# LEDMatrix_buffered.net
KiCad netlist of a schematic drawn in EAGLE
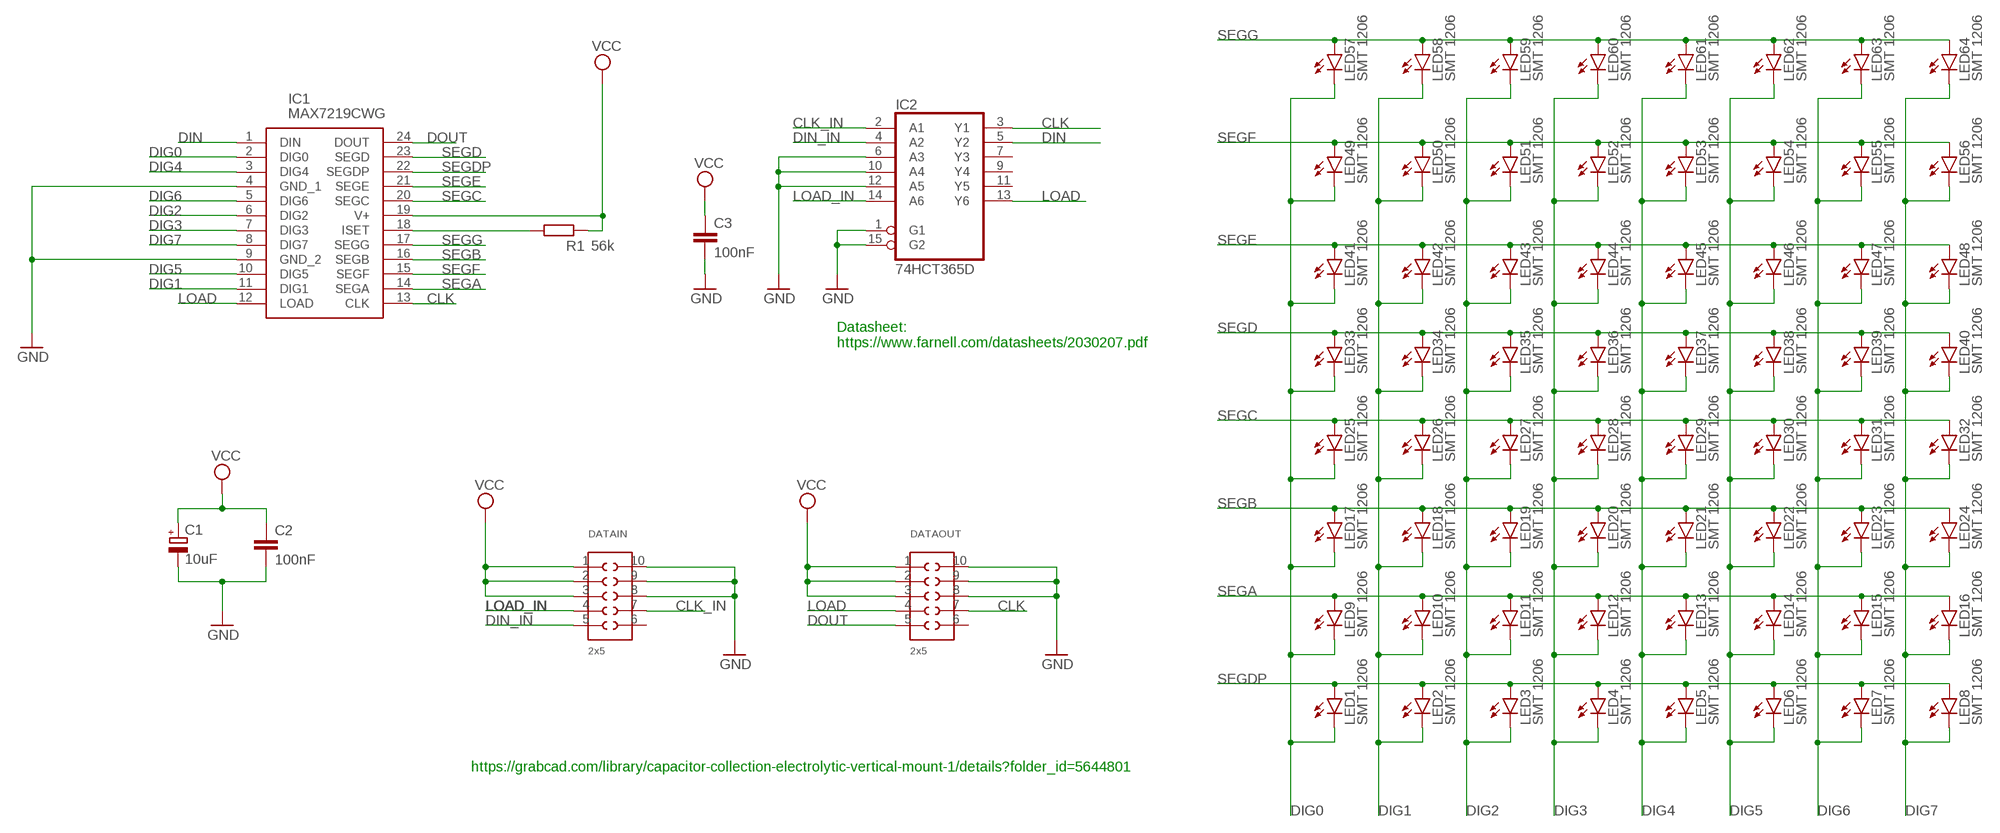
[diagram p0: schematic, sheet 1]

(export (version "E")
  (design (tool "Eeschema 10.0.6"))
  (components
    (comp (ref "C1")
      (value "10uF")
      (footprint "eagle-import:E5-8,5")
      (libsource (lib "eagle-import") (part "CPOL-EUE5-8.5"))
    )
    (comp (ref "C2")
      (value "100nF")
      (footprint "eagle-import:C1206")
      (libsource (lib "eagle-import") (part "C-EUC1206"))
    )
    (comp (ref "C3")
      (value "100nF")
      (footprint "eagle-import:C1206")
      (libsource (lib "eagle-import") (part "C-EUC1206"))
    )
    (comp (ref "DATAIN")
      (value "2x5")
      (footprint "eagle-import:610X1021121")
      (libsource (lib "eagle-import") (part "610X1021121"))
    )
    (comp (ref "DATAOUT")
      (value "2x5")
      (footprint "eagle-import:610X1021121")
      (libsource (lib "eagle-import") (part "610X1021121"))
    )
    (comp (ref "IC1")
      (value "MAX7219CWG")
      (footprint "eagle-import:SOIC127P1032X265-24N")
      (libsource (lib "eagle-import") (part "MAX7219CWG"))
    )
    (comp (ref "IC2")
      (value "74HCT365D")
      (footprint "eagle-import:SO16")
      (fields (field (name "SPICEPREFIX") "X"))
      (libsource (lib "eagle-import") (part "74365DHCT"))
    )
    (comp (ref "LED1")
      (value "SMT 1206")
      (footprint "eagle-import:CHIPLED_1206")
      (libsource (lib "eagle-import") (part "LEDCHIPLED_1206"))
    )
    (comp (ref "LED2")
      (value "SMT 1206")
      (footprint "eagle-import:CHIPLED_1206")
      (libsource (lib "eagle-import") (part "LEDCHIPLED_1206"))
    )
    (comp (ref "LED3")
      (value "SMT 1206")
      (footprint "eagle-import:CHIPLED_1206")
      (libsource (lib "eagle-import") (part "LEDCHIPLED_1206"))
    )
    (comp (ref "LED4")
      (value "SMT 1206")
      (footprint "eagle-import:CHIPLED_1206")
      (libsource (lib "eagle-import") (part "LEDCHIPLED_1206"))
    )
    (comp (ref "LED5")
      (value "SMT 1206")
      (footprint "eagle-import:CHIPLED_1206")
      (libsource (lib "eagle-import") (part "LEDCHIPLED_1206"))
    )
    (comp (ref "LED6")
      (value "SMT 1206")
      (footprint "eagle-import:CHIPLED_1206")
      (libsource (lib "eagle-import") (part "LEDCHIPLED_1206"))
    )
    (comp (ref "LED7")
      (value "SMT 1206")
      (footprint "eagle-import:CHIPLED_1206")
      (libsource (lib "eagle-import") (part "LEDCHIPLED_1206"))
    )
    (comp (ref "LED8")
      (value "SMT 1206")
      (footprint "eagle-import:CHIPLED_1206")
      (libsource (lib "eagle-import") (part "LEDCHIPLED_1206"))
    )
    (comp (ref "LED9")
      (value "SMT 1206")
      (footprint "eagle-import:CHIPLED_1206")
      (libsource (lib "eagle-import") (part "LEDCHIPLED_1206"))
    )
    (comp (ref "LED10")
      (value "SMT 1206")
      (footprint "eagle-import:CHIPLED_1206")
      (libsource (lib "eagle-import") (part "LEDCHIPLED_1206"))
    )
    (comp (ref "LED11")
      (value "SMT 1206")
      (footprint "eagle-import:CHIPLED_1206")
      (libsource (lib "eagle-import") (part "LEDCHIPLED_1206"))
    )
    (comp (ref "LED12")
      (value "SMT 1206")
      (footprint "eagle-import:CHIPLED_1206")
      (libsource (lib "eagle-import") (part "LEDCHIPLED_1206"))
    )
    (comp (ref "LED13")
      (value "SMT 1206")
      (footprint "eagle-import:CHIPLED_1206")
      (libsource (lib "eagle-import") (part "LEDCHIPLED_1206"))
    )
    (comp (ref "LED14")
      (value "SMT 1206")
      (footprint "eagle-import:CHIPLED_1206")
      (libsource (lib "eagle-import") (part "LEDCHIPLED_1206"))
    )
    (comp (ref "LED15")
      (value "SMT 1206")
      (footprint "eagle-import:CHIPLED_1206")
      (libsource (lib "eagle-import") (part "LEDCHIPLED_1206"))
    )
    (comp (ref "LED16")
      (value "SMT 1206")
      (footprint "eagle-import:CHIPLED_1206")
      (libsource (lib "eagle-import") (part "LEDCHIPLED_1206"))
    )
    (comp (ref "LED17")
      (value "SMT 1206")
      (footprint "eagle-import:CHIPLED_1206")
      (libsource (lib "eagle-import") (part "LEDCHIPLED_1206"))
    )
    (comp (ref "LED18")
      (value "SMT 1206")
      (footprint "eagle-import:CHIPLED_1206")
      (libsource (lib "eagle-import") (part "LEDCHIPLED_1206"))
    )
    (comp (ref "LED19")
      (value "SMT 1206")
      (footprint "eagle-import:CHIPLED_1206")
      (libsource (lib "eagle-import") (part "LEDCHIPLED_1206"))
    )
    (comp (ref "LED20")
      (value "SMT 1206")
      (footprint "eagle-import:CHIPLED_1206")
      (libsource (lib "eagle-import") (part "LEDCHIPLED_1206"))
    )
    (comp (ref "LED21")
      (value "SMT 1206")
      (footprint "eagle-import:CHIPLED_1206")
      (libsource (lib "eagle-import") (part "LEDCHIPLED_1206"))
    )
    (comp (ref "LED22")
      (value "SMT 1206")
      (footprint "eagle-import:CHIPLED_1206")
      (libsource (lib "eagle-import") (part "LEDCHIPLED_1206"))
    )
    (comp (ref "LED23")
      (value "SMT 1206")
      (footprint "eagle-import:CHIPLED_1206")
      (libsource (lib "eagle-import") (part "LEDCHIPLED_1206"))
    )
    (comp (ref "LED24")
      (value "SMT 1206")
      (footprint "eagle-import:CHIPLED_1206")
      (libsource (lib "eagle-import") (part "LEDCHIPLED_1206"))
    )
    (comp (ref "LED25")
      (value "SMT 1206")
      (footprint "eagle-import:CHIPLED_1206")
      (libsource (lib "eagle-import") (part "LEDCHIPLED_1206"))
    )
    (comp (ref "LED26")
      (value "SMT 1206")
      (footprint "eagle-import:CHIPLED_1206")
      (libsource (lib "eagle-import") (part "LEDCHIPLED_1206"))
    )
    (comp (ref "LED27")
      (value "SMT 1206")
      (footprint "eagle-import:CHIPLED_1206")
      (libsource (lib "eagle-import") (part "LEDCHIPLED_1206"))
    )
    (comp (ref "LED28")
      (value "SMT 1206")
      (footprint "eagle-import:CHIPLED_1206")
      (libsource (lib "eagle-import") (part "LEDCHIPLED_1206"))
    )
    (comp (ref "LED29")
      (value "SMT 1206")
      (footprint "eagle-import:CHIPLED_1206")
      (libsource (lib "eagle-import") (part "LEDCHIPLED_1206"))
    )
    (comp (ref "LED30")
      (value "SMT 1206")
      (footprint "eagle-import:CHIPLED_1206")
      (libsource (lib "eagle-import") (part "LEDCHIPLED_1206"))
    )
    (comp (ref "LED31")
      (value "SMT 1206")
      (footprint "eagle-import:CHIPLED_1206")
      (libsource (lib "eagle-import") (part "LEDCHIPLED_1206"))
    )
    (comp (ref "LED32")
      (value "SMT 1206")
      (footprint "eagle-import:CHIPLED_1206")
      (libsource (lib "eagle-import") (part "LEDCHIPLED_1206"))
    )
    (comp (ref "LED33")
      (value "SMT 1206")
      (footprint "eagle-import:CHIPLED_1206")
      (libsource (lib "eagle-import") (part "LEDCHIPLED_1206"))
    )
    (comp (ref "LED34")
      (value "SMT 1206")
      (footprint "eagle-import:CHIPLED_1206")
      (libsource (lib "eagle-import") (part "LEDCHIPLED_1206"))
    )
    (comp (ref "LED35")
      (value "SMT 1206")
      (footprint "eagle-import:CHIPLED_1206")
      (libsource (lib "eagle-import") (part "LEDCHIPLED_1206"))
    )
    (comp (ref "LED36")
      (value "SMT 1206")
      (footprint "eagle-import:CHIPLED_1206")
      (libsource (lib "eagle-import") (part "LEDCHIPLED_1206"))
    )
    (comp (ref "LED37")
      (value "SMT 1206")
      (footprint "eagle-import:CHIPLED_1206")
      (libsource (lib "eagle-import") (part "LEDCHIPLED_1206"))
    )
    (comp (ref "LED38")
      (value "SMT 1206")
      (footprint "eagle-import:CHIPLED_1206")
      (libsource (lib "eagle-import") (part "LEDCHIPLED_1206"))
    )
    (comp (ref "LED39")
      (value "SMT 1206")
      (footprint "eagle-import:CHIPLED_1206")
      (libsource (lib "eagle-import") (part "LEDCHIPLED_1206"))
    )
    (comp (ref "LED40")
      (value "SMT 1206")
      (footprint "eagle-import:CHIPLED_1206")
      (libsource (lib "eagle-import") (part "LEDCHIPLED_1206"))
    )
    (comp (ref "LED41")
      (value "SMT 1206")
      (footprint "eagle-import:CHIPLED_1206")
      (libsource (lib "eagle-import") (part "LEDCHIPLED_1206"))
    )
    (comp (ref "LED42")
      (value "SMT 1206")
      (footprint "eagle-import:CHIPLED_1206")
      (libsource (lib "eagle-import") (part "LEDCHIPLED_1206"))
    )
    (comp (ref "LED43")
      (value "SMT 1206")
      (footprint "eagle-import:CHIPLED_1206")
      (libsource (lib "eagle-import") (part "LEDCHIPLED_1206"))
    )
    (comp (ref "LED44")
      (value "SMT 1206")
      (footprint "eagle-import:CHIPLED_1206")
      (libsource (lib "eagle-import") (part "LEDCHIPLED_1206"))
    )
    (comp (ref "LED45")
      (value "SMT 1206")
      (footprint "eagle-import:CHIPLED_1206")
      (libsource (lib "eagle-import") (part "LEDCHIPLED_1206"))
    )
    (comp (ref "LED46")
      (value "SMT 1206")
      (footprint "eagle-import:CHIPLED_1206")
      (libsource (lib "eagle-import") (part "LEDCHIPLED_1206"))
    )
    (comp (ref "LED47")
      (value "SMT 1206")
      (footprint "eagle-import:CHIPLED_1206")
      (libsource (lib "eagle-import") (part "LEDCHIPLED_1206"))
    )
    (comp (ref "LED48")
      (value "SMT 1206")
      (footprint "eagle-import:CHIPLED_1206")
      (libsource (lib "eagle-import") (part "LEDCHIPLED_1206"))
    )
    (comp (ref "LED49")
      (value "SMT 1206")
      (footprint "eagle-import:CHIPLED_1206")
      (libsource (lib "eagle-import") (part "LEDCHIPLED_1206"))
    )
    (comp (ref "LED50")
      (value "SMT 1206")
      (footprint "eagle-import:CHIPLED_1206")
      (libsource (lib "eagle-import") (part "LEDCHIPLED_1206"))
    )
    (comp (ref "LED51")
      (value "SMT 1206")
      (footprint "eagle-import:CHIPLED_1206")
      (libsource (lib "eagle-import") (part "LEDCHIPLED_1206"))
    )
    (comp (ref "LED52")
      (value "SMT 1206")
      (footprint "eagle-import:CHIPLED_1206")
      (libsource (lib "eagle-import") (part "LEDCHIPLED_1206"))
    )
    (comp (ref "LED53")
      (value "SMT 1206")
      (footprint "eagle-import:CHIPLED_1206")
      (libsource (lib "eagle-import") (part "LEDCHIPLED_1206"))
    )
    (comp (ref "LED54")
      (value "SMT 1206")
      (footprint "eagle-import:CHIPLED_1206")
      (libsource (lib "eagle-import") (part "LEDCHIPLED_1206"))
    )
    (comp (ref "LED55")
      (value "SMT 1206")
      (footprint "eagle-import:CHIPLED_1206")
      (libsource (lib "eagle-import") (part "LEDCHIPLED_1206"))
    )
    (comp (ref "LED56")
      (value "SMT 1206")
      (footprint "eagle-import:CHIPLED_1206")
      (libsource (lib "eagle-import") (part "LEDCHIPLED_1206"))
    )
    (comp (ref "LED57")
      (value "SMT 1206")
      (footprint "eagle-import:CHIPLED_1206")
      (libsource (lib "eagle-import") (part "LEDCHIPLED_1206"))
    )
    (comp (ref "LED58")
      (value "SMT 1206")
      (footprint "eagle-import:CHIPLED_1206")
      (libsource (lib "eagle-import") (part "LEDCHIPLED_1206"))
    )
    (comp (ref "LED59")
      (value "SMT 1206")
      (footprint "eagle-import:CHIPLED_1206")
      (libsource (lib "eagle-import") (part "LEDCHIPLED_1206"))
    )
    (comp (ref "LED60")
      (value "SMT 1206")
      (footprint "eagle-import:CHIPLED_1206")
      (libsource (lib "eagle-import") (part "LEDCHIPLED_1206"))
    )
    (comp (ref "LED61")
      (value "SMT 1206")
      (footprint "eagle-import:CHIPLED_1206")
      (libsource (lib "eagle-import") (part "LEDCHIPLED_1206"))
    )
    (comp (ref "LED62")
      (value "SMT 1206")
      (footprint "eagle-import:CHIPLED_1206")
      (libsource (lib "eagle-import") (part "LEDCHIPLED_1206"))
    )
    (comp (ref "LED63")
      (value "SMT 1206")
      (footprint "eagle-import:CHIPLED_1206")
      (libsource (lib "eagle-import") (part "LEDCHIPLED_1206"))
    )
    (comp (ref "LED64")
      (value "SMT 1206")
      (footprint "eagle-import:CHIPLED_1206")
      (libsource (lib "eagle-import") (part "LEDCHIPLED_1206"))
    )
    (comp (ref "R1")
      (value "56k")
      (footprint "eagle-import:R1206")
      (libsource (lib "eagle-import") (part "R-EU_R1206"))
    )
  )
  (nets
    (net (code "1") (name "/CLK") (class "Default")
      (node (ref "DATAOUT") (pin "7") (pinfunction "7_7") (pintype "passive"))
      (node (ref "IC1") (pin "13") (pinfunction "CLK_13") (pintype "bidirectional"))
      (node (ref "IC2") (pin "3") (pinfunction "Y1_3") (pintype "tri_state"))
    )
    (net (code "2") (name "/CLK_IN") (class "Default")
      (node (ref "DATAIN") (pin "7") (pinfunction "7_7") (pintype "passive"))
      (node (ref "IC2") (pin "2") (pinfunction "A1_2") (pintype "input"))
    )
    (net (code "3") (name "/DIG0") (class "Default")
      (node (ref "IC1") (pin "2") (pinfunction "DIG0_2") (pintype "bidirectional"))
      (node (ref "LED1") (pin "C") (pinfunction "C_C") (pintype "passive"))
      (node (ref "LED17") (pin "C") (pinfunction "C_C") (pintype "passive"))
      (node (ref "LED25") (pin "C") (pinfunction "C_C") (pintype "passive"))
      (node (ref "LED33") (pin "C") (pinfunction "C_C") (pintype "passive"))
      (node (ref "LED41") (pin "C") (pinfunction "C_C") (pintype "passive"))
      (node (ref "LED49") (pin "C") (pinfunction "C_C") (pintype "passive"))
      (node (ref "LED57") (pin "C") (pinfunction "C_C") (pintype "passive"))
      (node (ref "LED9") (pin "C") (pinfunction "C_C") (pintype "passive"))
    )
    (net (code "4") (name "/DIG1") (class "Default")
      (node (ref "IC1") (pin "11") (pinfunction "DIG1_11") (pintype "bidirectional"))
      (node (ref "LED10") (pin "C") (pinfunction "C_C") (pintype "passive"))
      (node (ref "LED18") (pin "C") (pinfunction "C_C") (pintype "passive"))
      (node (ref "LED2") (pin "C") (pinfunction "C_C") (pintype "passive"))
      (node (ref "LED26") (pin "C") (pinfunction "C_C") (pintype "passive"))
      (node (ref "LED34") (pin "C") (pinfunction "C_C") (pintype "passive"))
      (node (ref "LED42") (pin "C") (pinfunction "C_C") (pintype "passive"))
      (node (ref "LED50") (pin "C") (pinfunction "C_C") (pintype "passive"))
      (node (ref "LED58") (pin "C") (pinfunction "C_C") (pintype "passive"))
    )
    (net (code "5") (name "/DIG2") (class "Default")
      (node (ref "IC1") (pin "6") (pinfunction "DIG2_6") (pintype "bidirectional"))
      (node (ref "LED11") (pin "C") (pinfunction "C_C") (pintype "passive"))
      (node (ref "LED19") (pin "C") (pinfunction "C_C") (pintype "passive"))
      (node (ref "LED27") (pin "C") (pinfunction "C_C") (pintype "passive"))
      (node (ref "LED3") (pin "C") (pinfunction "C_C") (pintype "passive"))
      (node (ref "LED35") (pin "C") (pinfunction "C_C") (pintype "passive"))
      (node (ref "LED43") (pin "C") (pinfunction "C_C") (pintype "passive"))
      (node (ref "LED51") (pin "C") (pinfunction "C_C") (pintype "passive"))
      (node (ref "LED59") (pin "C") (pinfunction "C_C") (pintype "passive"))
    )
    (net (code "6") (name "/DIG3") (class "Default")
      (node (ref "IC1") (pin "7") (pinfunction "DIG3_7") (pintype "bidirectional"))
      (node (ref "LED12") (pin "C") (pinfunction "C_C") (pintype "passive"))
      (node (ref "LED20") (pin "C") (pinfunction "C_C") (pintype "passive"))
      (node (ref "LED28") (pin "C") (pinfunction "C_C") (pintype "passive"))
      (node (ref "LED36") (pin "C") (pinfunction "C_C") (pintype "passive"))
      (node (ref "LED4") (pin "C") (pinfunction "C_C") (pintype "passive"))
      (node (ref "LED44") (pin "C") (pinfunction "C_C") (pintype "passive"))
      (node (ref "LED52") (pin "C") (pinfunction "C_C") (pintype "passive"))
      (node (ref "LED60") (pin "C") (pinfunction "C_C") (pintype "passive"))
    )
    (net (code "7") (name "/DIG4") (class "Default")
      (node (ref "IC1") (pin "3") (pinfunction "DIG4_3") (pintype "bidirectional"))
      (node (ref "LED13") (pin "C") (pinfunction "C_C") (pintype "passive"))
      (node (ref "LED21") (pin "C") (pinfunction "C_C") (pintype "passive"))
      (node (ref "LED29") (pin "C") (pinfunction "C_C") (pintype "passive"))
      (node (ref "LED37") (pin "C") (pinfunction "C_C") (pintype "passive"))
      (node (ref "LED45") (pin "C") (pinfunction "C_C") (pintype "passive"))
      (node (ref "LED5") (pin "C") (pinfunction "C_C") (pintype "passive"))
      (node (ref "LED53") (pin "C") (pinfunction "C_C") (pintype "passive"))
      (node (ref "LED61") (pin "C") (pinfunction "C_C") (pintype "passive"))
    )
    (net (code "8") (name "/DIG5") (class "Default")
      (node (ref "IC1") (pin "10") (pinfunction "DIG5_10") (pintype "bidirectional"))
      (node (ref "LED14") (pin "C") (pinfunction "C_C") (pintype "passive"))
      (node (ref "LED22") (pin "C") (pinfunction "C_C") (pintype "passive"))
      (node (ref "LED30") (pin "C") (pinfunction "C_C") (pintype "passive"))
      (node (ref "LED38") (pin "C") (pinfunction "C_C") (pintype "passive"))
      (node (ref "LED46") (pin "C") (pinfunction "C_C") (pintype "passive"))
      (node (ref "LED54") (pin "C") (pinfunction "C_C") (pintype "passive"))
      (node (ref "LED6") (pin "C") (pinfunction "C_C") (pintype "passive"))
      (node (ref "LED62") (pin "C") (pinfunction "C_C") (pintype "passive"))
    )
    (net (code "9") (name "/DIG6") (class "Default")
      (node (ref "IC1") (pin "5") (pinfunction "DIG6_5") (pintype "bidirectional"))
      (node (ref "LED15") (pin "C") (pinfunction "C_C") (pintype "passive"))
      (node (ref "LED23") (pin "C") (pinfunction "C_C") (pintype "passive"))
      (node (ref "LED31") (pin "C") (pinfunction "C_C") (pintype "passive"))
      (node (ref "LED39") (pin "C") (pinfunction "C_C") (pintype "passive"))
      (node (ref "LED47") (pin "C") (pinfunction "C_C") (pintype "passive"))
      (node (ref "LED55") (pin "C") (pinfunction "C_C") (pintype "passive"))
      (node (ref "LED63") (pin "C") (pinfunction "C_C") (pintype "passive"))
      (node (ref "LED7") (pin "C") (pinfunction "C_C") (pintype "passive"))
    )
    (net (code "10") (name "/DIG7") (class "Default")
      (node (ref "IC1") (pin "8") (pinfunction "DIG7_8") (pintype "bidirectional"))
      (node (ref "LED16") (pin "C") (pinfunction "C_C") (pintype "passive"))
      (node (ref "LED24") (pin "C") (pinfunction "C_C") (pintype "passive"))
      (node (ref "LED32") (pin "C") (pinfunction "C_C") (pintype "passive"))
      (node (ref "LED40") (pin "C") (pinfunction "C_C") (pintype "passive"))
      (node (ref "LED48") (pin "C") (pinfunction "C_C") (pintype "passive"))
      (node (ref "LED56") (pin "C") (pinfunction "C_C") (pintype "passive"))
      (node (ref "LED64") (pin "C") (pinfunction "C_C") (pintype "passive"))
      (node (ref "LED8") (pin "C") (pinfunction "C_C") (pintype "passive"))
    )
    (net (code "11") (name "/DIN") (class "Default")
      (node (ref "IC1") (pin "1") (pinfunction "DIN_1") (pintype "bidirectional"))
      (node (ref "IC2") (pin "5") (pinfunction "Y2_5") (pintype "tri_state"))
    )
    (net (code "12") (name "/DIN_IN") (class "Default")
      (node (ref "DATAIN") (pin "5") (pinfunction "5_5") (pintype "passive"))
      (node (ref "IC2") (pin "4") (pinfunction "A2_4") (pintype "input"))
    )
    (net (code "13") (name "/DOUT") (class "Default")
      (node (ref "DATAOUT") (pin "5") (pinfunction "5_5") (pintype "passive"))
      (node (ref "IC1") (pin "24") (pinfunction "DOUT_24") (pintype "bidirectional"))
    )
    (net (code "14") (name "/LOAD") (class "Default")
      (node (ref "DATAOUT") (pin "4") (pinfunction "4_4") (pintype "passive"))
      (node (ref "IC1") (pin "12") (pinfunction "LOAD_12") (pintype "bidirectional"))
      (node (ref "IC2") (pin "13") (pinfunction "Y6_13") (pintype "tri_state"))
    )
    (net (code "15") (name "/LOAD_IN") (class "Default")
      (node (ref "DATAIN") (pin "4") (pinfunction "4_4") (pintype "passive"))
      (node (ref "IC2") (pin "14") (pinfunction "A6_14") (pintype "input"))
    )
    (net (code "16") (name "/SEGA") (class "Default")
      (node (ref "IC1") (pin "14") (pinfunction "SEGA_14") (pintype "bidirectional"))
      (node (ref "LED10") (pin "A") (pinfunction "A_A") (pintype "passive"))
      (node (ref "LED11") (pin "A") (pinfunction "A_A") (pintype "passive"))
      (node (ref "LED12") (pin "A") (pinfunction "A_A") (pintype "passive"))
      (node (ref "LED13") (pin "A") (pinfunction "A_A") (pintype "passive"))
      (node (ref "LED14") (pin "A") (pinfunction "A_A") (pintype "passive"))
      (node (ref "LED15") (pin "A") (pinfunction "A_A") (pintype "passive"))
      (node (ref "LED16") (pin "A") (pinfunction "A_A") (pintype "passive"))
      (node (ref "LED9") (pin "A") (pinfunction "A_A") (pintype "passive"))
    )
    (net (code "17") (name "/SEGB") (class "Default")
      (node (ref "IC1") (pin "16") (pinfunction "SEGB_16") (pintype "bidirectional"))
      (node (ref "LED17") (pin "A") (pinfunction "A_A") (pintype "passive"))
      (node (ref "LED18") (pin "A") (pinfunction "A_A") (pintype "passive"))
      (node (ref "LED19") (pin "A") (pinfunction "A_A") (pintype "passive"))
      (node (ref "LED20") (pin "A") (pinfunction "A_A") (pintype "passive"))
      (node (ref "LED21") (pin "A") (pinfunction "A_A") (pintype "passive"))
      (node (ref "LED22") (pin "A") (pinfunction "A_A") (pintype "passive"))
      (node (ref "LED23") (pin "A") (pinfunction "A_A") (pintype "passive"))
      (node (ref "LED24") (pin "A") (pinfunction "A_A") (pintype "passive"))
    )
    (net (code "18") (name "/SEGC") (class "Default")
      (node (ref "IC1") (pin "20") (pinfunction "SEGC_20") (pintype "bidirectional"))
      (node (ref "LED25") (pin "A") (pinfunction "A_A") (pintype "passive"))
      (node (ref "LED26") (pin "A") (pinfunction "A_A") (pintype "passive"))
      (node (ref "LED27") (pin "A") (pinfunction "A_A") (pintype "passive"))
      (node (ref "LED28") (pin "A") (pinfunction "A_A") (pintype "passive"))
      (node (ref "LED29") (pin "A") (pinfunction "A_A") (pintype "passive"))
      (node (ref "LED30") (pin "A") (pinfunction "A_A") (pintype "passive"))
      (node (ref "LED31") (pin "A") (pinfunction "A_A") (pintype "passive"))
      (node (ref "LED32") (pin "A") (pinfunction "A_A") (pintype "passive"))
    )
    (net (code "19") (name "/SEGD") (class "Default")
      (node (ref "IC1") (pin "23") (pinfunction "SEGD_23") (pintype "bidirectional"))
      (node (ref "LED33") (pin "A") (pinfunction "A_A") (pintype "passive"))
      (node (ref "LED34") (pin "A") (pinfunction "A_A") (pintype "passive"))
      (node (ref "LED35") (pin "A") (pinfunction "A_A") (pintype "passive"))
      (node (ref "LED36") (pin "A") (pinfunction "A_A") (pintype "passive"))
      (node (ref "LED37") (pin "A") (pinfunction "A_A") (pintype "passive"))
      (node (ref "LED38") (pin "A") (pinfunction "A_A") (pintype "passive"))
      (node (ref "LED39") (pin "A") (pinfunction "A_A") (pintype "passive"))
      (node (ref "LED40") (pin "A") (pinfunction "A_A") (pintype "passive"))
    )
    (net (code "20") (name "/SEGDP") (class "Default")
      (node (ref "IC1") (pin "22") (pinfunction "SEGDP_22") (pintype "bidirectional"))
      (node (ref "LED1") (pin "A") (pinfunction "A_A") (pintype "passive"))
      (node (ref "LED2") (pin "A") (pinfunction "A_A") (pintype "passive"))
      (node (ref "LED3") (pin "A") (pinfunction "A_A") (pintype "passive"))
      (node (ref "LED4") (pin "A") (pinfunction "A_A") (pintype "passive"))
      (node (ref "LED5") (pin "A") (pinfunction "A_A") (pintype "passive"))
      (node (ref "LED6") (pin "A") (pinfunction "A_A") (pintype "passive"))
      (node (ref "LED7") (pin "A") (pinfunction "A_A") (pintype "passive"))
      (node (ref "LED8") (pin "A") (pinfunction "A_A") (pintype "passive"))
    )
    (net (code "21") (name "/SEGE") (class "Default")
      (node (ref "IC1") (pin "21") (pinfunction "SEGE_21") (pintype "bidirectional"))
      (node (ref "LED41") (pin "A") (pinfunction "A_A") (pintype "passive"))
      (node (ref "LED42") (pin "A") (pinfunction "A_A") (pintype "passive"))
      (node (ref "LED43") (pin "A") (pinfunction "A_A") (pintype "passive"))
      (node (ref "LED44") (pin "A") (pinfunction "A_A") (pintype "passive"))
      (node (ref "LED45") (pin "A") (pinfunction "A_A") (pintype "passive"))
      (node (ref "LED46") (pin "A") (pinfunction "A_A") (pintype "passive"))
      (node (ref "LED47") (pin "A") (pinfunction "A_A") (pintype "passive"))
      (node (ref "LED48") (pin "A") (pinfunction "A_A") (pintype "passive"))
    )
    (net (code "22") (name "/SEGF") (class "Default")
      (node (ref "IC1") (pin "15") (pinfunction "SEGF_15") (pintype "bidirectional"))
      (node (ref "LED49") (pin "A") (pinfunction "A_A") (pintype "passive"))
      (node (ref "LED50") (pin "A") (pinfunction "A_A") (pintype "passive"))
      (node (ref "LED51") (pin "A") (pinfunction "A_A") (pintype "passive"))
      (node (ref "LED52") (pin "A") (pinfunction "A_A") (pintype "passive"))
      (node (ref "LED53") (pin "A") (pinfunction "A_A") (pintype "passive"))
      (node (ref "LED54") (pin "A") (pinfunction "A_A") (pintype "passive"))
      (node (ref "LED55") (pin "A") (pinfunction "A_A") (pintype "passive"))
      (node (ref "LED56") (pin "A") (pinfunction "A_A") (pintype "passive"))
    )
    (net (code "23") (name "/SEGG") (class "Default")
      (node (ref "IC1") (pin "17") (pinfunction "SEGG_17") (pintype "bidirectional"))
      (node (ref "LED57") (pin "A") (pinfunction "A_A") (pintype "passive"))
      (node (ref "LED58") (pin "A") (pinfunction "A_A") (pintype "passive"))
      (node (ref "LED59") (pin "A") (pinfunction "A_A") (pintype "passive"))
      (node (ref "LED60") (pin "A") (pinfunction "A_A") (pintype "passive"))
      (node (ref "LED61") (pin "A") (pinfunction "A_A") (pintype "passive"))
      (node (ref "LED62") (pin "A") (pinfunction "A_A") (pintype "passive"))
      (node (ref "LED63") (pin "A") (pinfunction "A_A") (pintype "passive"))
      (node (ref "LED64") (pin "A") (pinfunction "A_A") (pintype "passive"))
    )
    (net (code "24") (name "GND") (class "Default")
      (node (ref "C1") (pin "-") (pinfunction "-_-") (pintype "passive"))
      (node (ref "C2") (pin "2") (pinfunction "2_2") (pintype "passive"))
      (node (ref "C3") (pin "2") (pinfunction "2_2") (pintype "passive"))
      (node (ref "DATAIN") (pin "10") (pinfunction "10_10") (pintype "passive"))
      (node (ref "DATAIN") (pin "8") (pinfunction "8_8") (pintype "passive"))
      (node (ref "DATAIN") (pin "9") (pinfunction "9_9") (pintype "passive"))
      (node (ref "DATAOUT") (pin "10") (pinfunction "10_10") (pintype "passive"))
      (node (ref "DATAOUT") (pin "8") (pinfunction "8_8") (pintype "passive"))
      (node (ref "DATAOUT") (pin "9") (pinfunction "9_9") (pintype "passive"))
      (node (ref "IC1") (pin "4") (pinfunction "GND_1_4") (pintype "bidirectional"))
      (node (ref "IC1") (pin "9") (pinfunction "GND_2_9") (pintype "bidirectional"))
      (node (ref "IC2") (pin "1") (pinfunction "G1_1") (pintype "input"))
      (node (ref "IC2") (pin "10") (pinfunction "A4_10") (pintype "input"))
      (node (ref "IC2") (pin "12") (pinfunction "A5_12") (pintype "input"))
      (node (ref "IC2") (pin "15") (pinfunction "G2_15") (pintype "input"))
      (node (ref "IC2") (pin "6") (pinfunction "A3_6") (pintype "input"))
    )
    (net (code "25") (name "Net-(IC1-ISET)") (class "Default")
      (node (ref "IC1") (pin "18") (pinfunction "ISET_18") (pintype "bidirectional"))
      (node (ref "R1") (pin "1") (pinfunction "1_1") (pintype "passive"))
    )
    (net (code "26") (name "VCC") (class "Default")
      (node (ref "C1") (pin "+") (pinfunction "+_+") (pintype "passive"))
      (node (ref "C2") (pin "1") (pinfunction "1_1") (pintype "passive"))
      (node (ref "C3") (pin "1") (pinfunction "1_1") (pintype "passive"))
      (node (ref "DATAIN") (pin "1") (pinfunction "1_1") (pintype "passive"))
      (node (ref "DATAIN") (pin "2") (pinfunction "2_2") (pintype "passive"))
      (node (ref "DATAIN") (pin "3") (pinfunction "3_3") (pintype "passive"))
      (node (ref "DATAOUT") (pin "1") (pinfunction "1_1") (pintype "passive"))
      (node (ref "DATAOUT") (pin "2") (pinfunction "2_2") (pintype "passive"))
      (node (ref "DATAOUT") (pin "3") (pinfunction "3_3") (pintype "passive"))
      (node (ref "IC1") (pin "19") (pinfunction "V+_19") (pintype "bidirectional"))
      (node (ref "R1") (pin "2") (pinfunction "2_2") (pintype "passive"))
    )
    (net (code "27") (name "unconnected-(DATAIN-Pad6)") (class "Default")
      (node (ref "DATAIN") (pin "6") (pinfunction "6_6") (pintype "passive"))
    )
    (net (code "28") (name "unconnected-(DATAOUT-Pad6)") (class "Default")
      (node (ref "DATAOUT") (pin "6") (pinfunction "6_6") (pintype "passive"))
    )
    (net (code "29") (name "unconnected-(IC2A-Y3-Pad7)") (class "Default")
      (node (ref "IC2") (pin "7") (pinfunction "Y3_7") (pintype "tri_state"))
    )
    (net (code "30") (name "unconnected-(IC2A-Y4-Pad9)") (class "Default")
      (node (ref "IC2") (pin "9") (pinfunction "Y4_9") (pintype "tri_state"))
    )
    (net (code "31") (name "unconnected-(IC2A-Y5-Pad11)") (class "Default")
      (node (ref "IC2") (pin "11") (pinfunction "Y5_11") (pintype "tri_state"))
    )
  )
)
